# PCB_Emergencia.net
KiCad netlist of a schematic drawn in Altium Designer
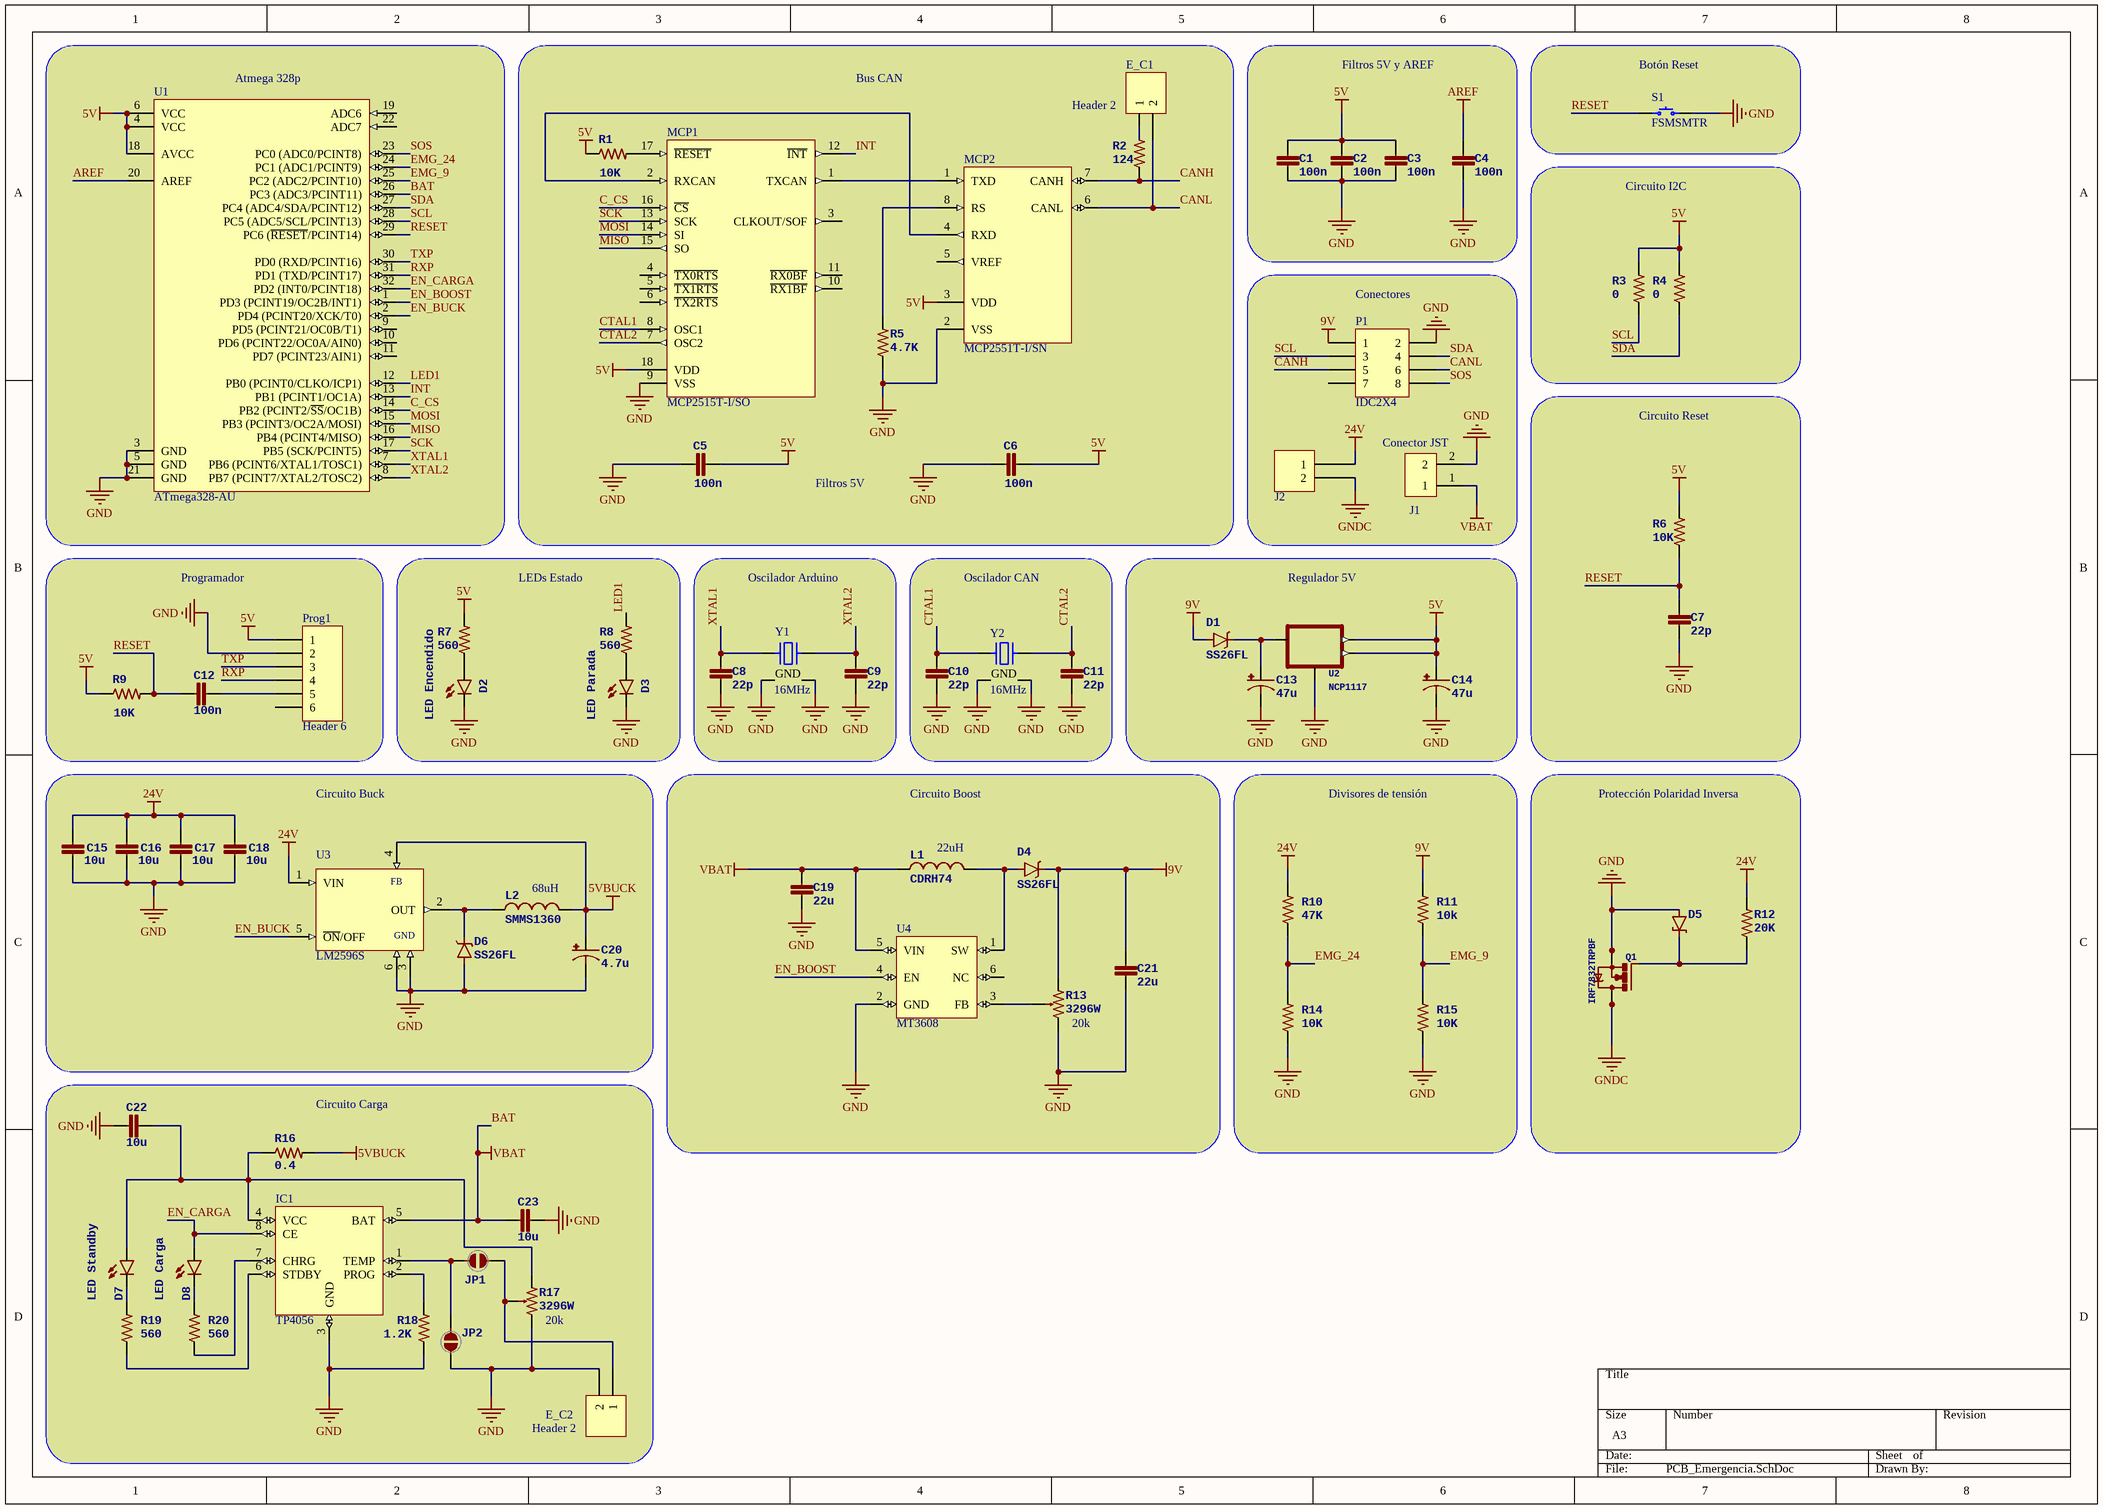
[diagram p0: PCB_Emergencia.SchDoc]

(export (version "E")
  (design (tool "Eeschema 10.0.6"))
  (components
    (comp (ref "C1")
      (value "CapacitorStandard 0603 ceramic capacitor, and 0.1\" leaded capacitor.")
      (footprint "SparkFun-Passives:0805")
      (fields (field (name "CAP") "100n"))
      (libsource (lib "") (part "CAP0805_3"))
    )
    (comp (ref "C2")
      (value "CapacitorStandard 0603 ceramic capacitor, and 0.1\" leaded capacitor.")
      (footprint "SparkFun-Passives:0805")
      (fields (field (name "CAP") "100n"))
      (libsource (lib "") (part "CAP0805_3"))
    )
    (comp (ref "C3")
      (value "CapacitorStandard 0603 ceramic capacitor, and 0.1\" leaded capacitor.")
      (footprint "SparkFun-Passives:0805")
      (fields (field (name "CAP") "100n"))
      (libsource (lib "") (part "CAP0805_3"))
    )
    (comp (ref "C4")
      (value "CapacitorStandard 0603 ceramic capacitor, and 0.1\" leaded capacitor.")
      (footprint "SparkFun-Passives:0805")
      (fields (field (name "CAP") "100n"))
      (libsource (lib "") (part "CAP0805_3"))
    )
    (comp (ref "C5")
      (value "CapacitorStandard 0603 ceramic capacitor, and 0.1\" leaded capacitor.")
      (footprint "SparkFun-Passives:0805")
      (fields (field (name "CAP") "100n"))
      (libsource (lib "") (part "CAP0805_2"))
    )
    (comp (ref "C6")
      (value "CapacitorStandard 0603 ceramic capacitor, and 0.1\" leaded capacitor.")
      (footprint "SparkFun-Passives:0805")
      (fields (field (name "CAP") "100n"))
      (libsource (lib "") (part "CAP0805_2"))
    )
    (comp (ref "C7")
      (value "CapacitorStandard 0603 ceramic capacitor, and 0.1\" leaded capacitor.")
      (footprint "SparkFun-Passives:0805")
      (fields (field (name "CAP") "22p"))
      (libsource (lib "") (part "CAP0805_3"))
    )
    (comp (ref "C8")
      (value "CapacitorStandard 0603 ceramic capacitor, and 0.1\" leaded capacitor.")
      (footprint "SparkFun-Passives:0805")
      (fields (field (name "CAP") "22p"))
      (libsource (lib "") (part "CAP0805_3"))
    )
    (comp (ref "C9")
      (value "CapacitorStandard 0603 ceramic capacitor, and 0.1\" leaded capacitor.")
      (footprint "SparkFun-Passives:0805")
      (fields (field (name "CAP") "22p"))
      (libsource (lib "") (part "CAP0805_1"))
    )
    (comp (ref "C10")
      (value "CapacitorStandard 0603 ceramic capacitor, and 0.1\" leaded capacitor.")
      (footprint "SparkFun-Passives:0805")
      (fields (field (name "CAP") "22p"))
      (libsource (lib "") (part "CAP0805_3"))
    )
    (comp (ref "C11")
      (value "CapacitorStandard 0603 ceramic capacitor, and 0.1\" leaded capacitor.")
      (footprint "SparkFun-Passives:0805")
      (fields (field (name "CAP") "22p"))
      (libsource (lib "") (part "CAP0805_1"))
    )
    (comp (ref "C12")
      (value "CapacitorStandard 0603 ceramic capacitor, and 0.1\" leaded capacitor.")
      (footprint "SparkFun-Passives:0805")
      (fields (field (name "CAP") "100n"))
      (libsource (lib "SparkFun-Capacitors") (part "CAP0805"))
    )
    (comp (ref "C13")
      (value "47u")
      (footprint "PANASONIC_D")
      (libsource (lib "SparkFun-Capacitors") (part "47UF-50V-20%(ELECT)"))
    )
    (comp (ref "C14")
      (value "47u")
      (footprint "PANASONIC_D")
      (libsource (lib "SparkFun-Capacitors") (part "47UF-50V-20%(ELECT)"))
    )
    (comp (ref "C15")
      (value "CapacitorStandard 0603 ceramic capacitor, and 0.1\" leaded capacitor.")
      (footprint "SparkFun-Passives:0805")
      (fields (field (name "CAP") "10u"))
      (libsource (lib "") (part "CAP0805_3"))
    )
    (comp (ref "C16")
      (value "CapacitorStandard 0603 ceramic capacitor, and 0.1\" leaded capacitor.")
      (footprint "SparkFun-Passives:0805")
      (fields (field (name "CAP") "10u"))
      (libsource (lib "") (part "CAP0805_3"))
    )
    (comp (ref "C17")
      (value "CapacitorStandard 0603 ceramic capacitor, and 0.1\" leaded capacitor.")
      (footprint "SparkFun-Passives:0805")
      (fields (field (name "CAP") "10u"))
      (libsource (lib "") (part "CAP0805_3"))
    )
    (comp (ref "C18")
      (value "CapacitorStandard 0603 ceramic capacitor, and 0.1\" leaded capacitor.")
      (footprint "SparkFun-Passives:0805")
      (fields (field (name "CAP") "10u"))
      (libsource (lib "") (part "CAP0805_3"))
    )
    (comp (ref "C19")
      (value "CapacitorStandard 0603 ceramic capacitor, and 0.1\" leaded capacitor.")
      (footprint "SparkFun-Passives:0805")
      (fields (field (name "CAP") "22u"))
      (libsource (lib "") (part "CAP0805_1"))
    )
    (comp (ref "C20")
      (value "4.7u")
      (footprint "PANASONIC_D")
      (libsource (lib "SparkFun-Capacitors") (part "47UF-50V-20%(ELECT)"))
    )
    (comp (ref "C21")
      (value "CapacitorStandard 0603 ceramic capacitor, and 0.1\" leaded capacitor.")
      (footprint "SparkFun-Passives:0805")
      (fields (field (name "CAP") "22u"))
      (libsource (lib "") (part "CAP0805_1"))
    )
    (comp (ref "C22")
      (value "CapacitorStandard 0603 ceramic capacitor, and 0.1\" leaded capacitor.")
      (footprint "SparkFun-Passives:0805")
      (fields (field (name "CAP") "10u"))
      (libsource (lib "SparkFun-Capacitors") (part "CAP0805"))
    )
    (comp (ref "C23")
      (value "CapacitorStandard 0603 ceramic capacitor, and 0.1\" leaded capacitor.")
      (footprint "SparkFun-Passives:0805")
      (fields (field (name "CAP") "10u"))
      (libsource (lib "") (part "CAP0805_2"))
    )
    (comp (ref "D1") (value "SS26FL") (footprint "SS26FL") (libsource (lib "SS26FL") (part "SS26FL")))
    (comp (ref "D2")
      (value "LED Encendido")
      (footprint "LED-1206")
      (libsource (lib "SparkFun-LED") (part "LED1206"))
    )
    (comp (ref "D3")
      (value "LED Parada")
      (footprint "LED-1206")
      (libsource (lib "SparkFun-LED") (part "LED1206"))
    )
    (comp (ref "D4") (value "SS26FL") (footprint "SS26FL") (libsource (lib "SS26FL") (part "SS26FL")))
    (comp (ref "D5")
      (value "13V Zener MM1Z13")
      (footprint "SOD-123")
      (libsource (lib "SparkFun-DiscreteSemi") (part "DIODE-ZENER16V"))
    )
    (comp (ref "D6") (value "SS26FL") (footprint "SS26FL") (libsource (lib "SS26FL") (part "SS26FL")))
    (comp (ref "D7")
      (value "LED Standby")
      (footprint "LED-1206")
      (libsource (lib "SparkFun-LED") (part "LED1206"))
    )
    (comp (ref "D8")
      (value "LED Carga")
      (footprint "LED-1206")
      (libsource (lib "SparkFun-LED") (part "LED1206"))
    )
    (comp (ref "E_C1")
      (value "Header 2")
      (footprint "HDR1X2")
      (description "Header, 2-Pin")
      (fields (field (name "PUBLISHER") "Altium Limited"))
      (libsource (lib "Miscellaneous Connectors") (part "Header 2"))
    )
    (comp (ref "E_C2")
      (value "Header 2")
      (footprint "HDR1X2")
      (description "Header, 2-Pin")
      (fields (field (name "PUBLISHER") "Altium Limited"))
      (libsource (lib "") (part "Header 2_1"))
    )
    (comp (ref "IC1")
      (value "TP4056")
      (footprint "*SOP-8")
      (fields (field (name "MF") "NanJing Top Power ASIC Corp."))
      (libsource (lib "TP4056") (part "TP4056"))
    )
    (comp (ref "J1")
      (value "Conector JST")
      (footprint "*JST_S2B-PH-K-S(LF)(SN)")
      (description "PH Series 2 Position 2.0 mm Through Hole Side Entry Shrouded Header")
      (fields (field (name "MP") "S2B-PH-K-S_LF__SN_") (field (name "MF") "JST Sales"))
      (libsource (lib "S2B-PH-K-S_LF__SN_") (part "S2B-PH-K-S(LF)(SN)"))
    )
    (comp (ref "J2")
      (value "20020110-D021A01LF")
      (footprint "FCI 06-381-2PIN")
      (description "TERM BLOCK HDR 2POS R/A 3.81MM")
      (fields (field (name "MANUFACTURER") "FCI") (field (name "VOLTAGE") "300V"))
      (libsource (lib "Connector - Terminal Block") (part "2 Pin"))
    )
    (comp (ref "JP1")
      (value "JUMPER-PAD-2-NC_BY_PASTE")
      (footprint "PAD-JUMPER-2-NC_BY_PASTE_YES_SILK")
      (libsource (lib "SparkFun-Passives") (part "JUMPER-PAD-2-NC_BY_PASTE"))
    )
    (comp (ref "JP2")
      (value "JUMPER-PAD-2-NC_BY_PASTE")
      (footprint "PAD-JUMPER-2-NC_BY_PASTE_YES_SILK")
      (libsource (lib "SparkFun-Passives") (part "JUMPER-PAD-2-NC_BY_PASTE"))
    )
    (comp (ref "L1")
      (value "CDRH74")
      (footprint "CDRH74")
      (fields (field (name "ALTIUM_VALUE") "22uH"))
      (libsource (lib "CDRH74") (part "CDRH74"))
    )
    (comp (ref "L2")
      (value "SMMS1360")
      (footprint "SMMS1360 - duplicate")
      (fields (field (name "ALTIUM_VALUE") "68uH"))
      (libsource (lib "SMMS1360") (part "INDUCTOR"))
    )
    (comp (ref "MCP1")
      (value "MCP2515T-I/SO")
      (footprint "SOIC-SO18_N")
      (description "Stand-Alone CAN Controller With SPI Interface, 18-Pin SOIC, Industrial Temperature, Tape and Reel")
      (fields (field (name "PUBLISHER") "Altium Limited"))
      (libsource (lib "Microchip Interface") (part "MCP2515T-I/SO"))
    )
    (comp (ref "MCP2")
      (value "MCP2551T-I/SN")
      (footprint "SOIC-SN8_N")
      (description "High-Speed CAN Transceiver, 8-Pin SOIC, Industrial Temperature, Tape and Reel")
      (fields (field (name "PUBLISHER") "Altium Limited"))
      (libsource (lib "Microchip Interface") (part "MCP2551T-I/SN"))
    )
    (comp (ref "P1")
      (value "IDC2X4")
      (footprint "IDC2X4")
      (description "Header, 4-Pin, Dual row")
      (fields (field (name "PUBLISHER") "Altium Limited"))
      (libsource (lib "IDC") (part "IDC2X4"))
    )
    (comp (ref "Prog1")
      (value "Header 6")
      (footprint "HDR1X6")
      (description "Header, 6-Pin")
      (fields (field (name "PUBLISHER") "Altium Limited"))
      (libsource (lib "Miscellaneous Connectors") (part "Header 6"))
    )
    (comp (ref "Q1")
      (value "IRF7832TRPBF")
      (footprint "transistor-power:SO-08")
      (libsource (lib "transistor-power") (part "N-MOSFET-SO8S"))
    )
    (comp (ref "R1")
      (value "ResistorBasic schematic elements and footprints for 0603, 1206, and PTH resistors.")
      (footprint "SparkFun-Passives:0805")
      (fields (field (name "RES") "10K"))
      (libsource (lib "SparkFun-Passives") (part "RESISTOR0805-RES"))
    )
    (comp (ref "R2")
      (value "ResistorBasic schematic elements and footprints for 0603, 1206, and PTH resistors.")
      (footprint "SparkFun-Passives:0805")
      (fields (field (name "RES") "124"))
      (libsource (lib "SparkFun-Passives") (part "RESISTOR0805-RES"))
    )
    (comp (ref "R3")
      (value "ResistorBasic schematic elements and footprints for 0603, 1206, and PTH resistors.")
      (footprint "SparkFun-Passives:0805")
      (fields (field (name "RES") "0"))
      (libsource (lib "SparkFun-Passives") (part "RESISTOR0805-RES"))
    )
    (comp (ref "R4")
      (value "ResistorBasic schematic elements and footprints for 0603, 1206, and PTH resistors.")
      (footprint "SparkFun-Passives:0805")
      (fields (field (name "RES") "0"))
      (libsource (lib "SparkFun-Passives") (part "RESISTOR0805-RES"))
    )
    (comp (ref "R5")
      (value "ResistorBasic schematic elements and footprints for 0603, 1206, and PTH resistors.")
      (footprint "SparkFun-Passives:0805")
      (fields (field (name "RES") "4.7K"))
      (libsource (lib "SparkFun-Passives") (part "RESISTOR0805-RES"))
    )
    (comp (ref "R6")
      (value "ResistorBasic schematic elements and footprints for 0603, 1206, and PTH resistors.")
      (footprint "SparkFun-Passives:0805")
      (fields (field (name "RES") "10K"))
      (libsource (lib "SparkFun-Passives") (part "RESISTOR0805-RES"))
    )
    (comp (ref "R7")
      (value "ResistorBasic schematic elements and footprints for 0603, 1206, and PTH resistors.")
      (footprint "SparkFun-Passives:0805")
      (fields (field (name "RES") "560"))
      (libsource (lib "SparkFun-Passives") (part "RESISTOR0805-RES"))
    )
    (comp (ref "R8")
      (value "ResistorBasic schematic elements and footprints for 0603, 1206, and PTH resistors.")
      (footprint "SparkFun-Passives:0805")
      (fields (field (name "RES") "560"))
      (libsource (lib "SparkFun-Passives") (part "RESISTOR0805-RES"))
    )
    (comp (ref "R9")
      (value "ResistorBasic schematic elements and footprints for 0603, 1206, and PTH resistors.")
      (footprint "SparkFun-Passives:0805")
      (fields (field (name "RES") "10K"))
      (libsource (lib "SparkFun-Passives") (part "RESISTOR0805-RES"))
    )
    (comp (ref "R10")
      (value "ResistorBasic schematic elements and footprints for 0603, 1206, and PTH resistors.")
      (footprint "SparkFun-Passives:0805")
      (fields (field (name "RES") "47K"))
      (libsource (lib "SparkFun-Passives") (part "RESISTOR0805-RES"))
    )
    (comp (ref "R11")
      (value "ResistorBasic schematic elements and footprints for 0603, 1206, and PTH resistors.")
      (footprint "SparkFun-Passives:0805")
      (fields (field (name "RES") "10k"))
      (libsource (lib "SparkFun-Passives") (part "RESISTOR0805-RES"))
    )
    (comp (ref "R12")
      (value "20K")
      (footprint "SparkFun-Passives:0805")
      (libsource (lib "SparkFun-Passives") (part "RESISTOR0805-RES"))
    )
    (comp (ref "R13")
      (value "3296W")
      (footprint "3296W")
      (fields (field (name "ALTIUM_VALUE") "20k"))
      (libsource (lib "3296W") (part "3296W"))
    )
    (comp (ref "R14")
      (value "ResistorBasic schematic elements and footprints for 0603, 1206, and PTH resistors.")
      (footprint "SparkFun-Passives:0805")
      (fields (field (name "RES") "10K"))
      (libsource (lib "SparkFun-Passives") (part "RESISTOR0805-RES"))
    )
    (comp (ref "R15")
      (value "ResistorBasic schematic elements and footprints for 0603, 1206, and PTH resistors.")
      (footprint "SparkFun-Passives:0805")
      (fields (field (name "RES") "10K"))
      (libsource (lib "SparkFun-Passives") (part "RESISTOR0805-RES"))
    )
    (comp (ref "R16")
      (value "ResistorBasic schematic elements and footprints for 0603, 1206, and PTH resistors.")
      (footprint "SparkFun-Passives:0805")
      (fields (field (name "RES") "0.4"))
      (libsource (lib "SparkFun-Passives") (part "RESISTOR0805-RES"))
    )
    (comp (ref "R17")
      (value "3296W")
      (footprint "3296W")
      (fields (field (name "ALTIUM_VALUE") "20k"))
      (libsource (lib "3296W") (part "3296W"))
    )
    (comp (ref "R18")
      (value "ResistorBasic schematic elements and footprints for 0603, 1206, and PTH resistors.")
      (footprint "SparkFun-Passives:0805")
      (fields (field (name "RES") "1.2K"))
      (libsource (lib "SparkFun-Passives") (part "RESISTOR0805-RES"))
    )
    (comp (ref "R19")
      (value "ResistorBasic schematic elements and footprints for 0603, 1206, and PTH resistors.")
      (footprint "SparkFun-Passives:0805")
      (fields (field (name "RES") "560"))
      (libsource (lib "SparkFun-Passives") (part "RESISTOR0805-RES"))
    )
    (comp (ref "R20")
      (value "ResistorBasic schematic elements and footprints for 0603, 1206, and PTH resistors.")
      (footprint "SparkFun-Passives:0805")
      (fields (field (name "RES") "560"))
      (libsource (lib "SparkFun-Passives") (part "RESISTOR0805-RES"))
    )
    (comp (ref "S1")
      (value "FSMSMTR")
      (footprint "TE FSMSMTR")
      (description "SWITCH TACTILE SPST-NO 0.05A 24V")
      (fields (field (name "MANUFACTURER") "TE Connectivity Alcoswitch Switches"))
      (libsource (lib "Button - Tactile") (part "SPST-NO 2 PIN"))
    )
    (comp (ref "U1")
      (value "ATmega328-AU")
      (footprint "32A_N")
      (fields (field (name "PUBLISHER") "Altium Limited"))
      (libsource (lib "Atmel Microcontroller 8-Bit megaAVR") (part "ATmega328-AU"))
    )
    (comp (ref "U2")
      (value "NCP1117")
      (footprint "SOT223")
      (libsource (lib "SparkFun-IC-Power") (part "V_REG_LM1117SOT223"))
    )
    (comp (ref "U3")
      (value "LM2596S")
      (footprint "LM2596S")
      (description "Semiconductors and Actives")
      (fields (field (name "MF") "Texas Instruments"))
      (libsource (lib "LM2596S") (part "LM2596S"))
    )
    (comp (ref "U4")
      (value "MT3608")
      (footprint "*SOT23-6")
      (description "High Efficiency 1.2MHz\r\n2A Step Up Converter")
      (fields (field (name "MF") "Aerosemi Technology Co., Ltd"))
      (libsource (lib "MT3608") (part "MT3608"))
    )
    (comp (ref "Y1")
      (value "16MHz")
      (footprint "NDK NX3225SA")
      (description "CRYSTAL 16.0000MHZ 8PF SMD")
      (fields (field (name "PART NUMBER") "NX3225SA-16.000MHZ-STD-CSR-1") (field (name "MANUFACTURER") "NDK"))
      (libsource (lib "Oscillator - Crystal") (part "NX3225SA-16.000MHZ-STD-CSR-1"))
    )
    (comp (ref "Y2")
      (value "16MHz")
      (footprint "NDK NX3225SA")
      (description "CRYSTAL 16.0000MHZ 8PF SMD")
      (fields (field (name "PART NUMBER") "NX3225SA-16.000MHZ-STD-CSR-1") (field (name "MANUFACTURER") "NDK"))
      (libsource (lib "Oscillator - Crystal") (part "NX3225SA-16.000MHZ-STD-CSR-1"))
    )
  )
  (nets
    (net (code "1") (name "/CANH") (class "Default")
      (node (ref "MCP2") (pin "7") (pinfunction "CANH_7") (pintype "bidirectional"))
      (node (ref "P1") (pin "5") (pinfunction "5_5") (pintype "passive"))
      (node (ref "R2") (pin "1") (pinfunction "1_1") (pintype "passive"))
    )
    (net (code "2") (name "/CANL") (class "Default")
      (node (ref "E_C1") (pin "2") (pinfunction "2_2") (pintype "passive"))
      (node (ref "MCP2") (pin "6") (pinfunction "CANL_6") (pintype "bidirectional"))
      (node (ref "P1") (pin "6") (pinfunction "6_6") (pintype "passive"))
    )
    (net (code "3") (name "/CTAL1") (class "Default")
      (node (ref "C10") (pin "2") (pinfunction "2_2") (pintype "passive"))
      (node (ref "MCP1") (pin "8") (pinfunction "OSC1_8") (pintype "input"))
      (node (ref "Y2") (pin "1") (pinfunction "1_1") (pintype "passive"))
    )
    (net (code "4") (name "/CTAL2") (class "Default")
      (node (ref "C11") (pin "1") (pinfunction "1_1") (pintype "passive"))
      (node (ref "MCP1") (pin "7") (pinfunction "OSC2_7") (pintype "output"))
      (node (ref "Y2") (pin "3") (pinfunction "3_3") (pintype "passive"))
    )
    (net (code "5") (name "/C_CS") (class "Default")
      (node (ref "MCP1") (pin "16") (pinfunction "~{CS}_16") (pintype "input"))
      (node (ref "U1") (pin "14") (pinfunction "PB2_(PCINT2/~{SS}/OC1B)_14") (pintype "bidirectional"))
    )
    (net (code "6") (name "/EMG_9") (class "Default")
      (node (ref "R11") (pin "1") (pinfunction "1_1") (pintype "passive"))
      (node (ref "R15") (pin "2") (pinfunction "2_2") (pintype "passive"))
      (node (ref "U1") (pin "25") (pinfunction "PC2_(ADC2/PCINT10)_25") (pintype "bidirectional"))
    )
    (net (code "7") (name "/EMG_24") (class "Default")
      (node (ref "R10") (pin "1") (pinfunction "1_1") (pintype "passive"))
      (node (ref "R14") (pin "2") (pinfunction "2_2") (pintype "passive"))
      (node (ref "U1") (pin "24") (pinfunction "PC1_(ADC1/PCINT9)_24") (pintype "bidirectional"))
    )
    (net (code "8") (name "/EN_BOOST") (class "Default")
      (node (ref "U1") (pin "1") (pinfunction "PD3_(PCINT19/OC2B/INT1)_1") (pintype "bidirectional"))
      (node (ref "U4") (pin "4") (pinfunction "EN_4") (pintype "bidirectional"))
    )
    (net (code "9") (name "/EN_BUCK") (class "Default")
      (node (ref "U1") (pin "2") (pinfunction "PD4_(PCINT20/XCK/T0)_2") (pintype "bidirectional"))
      (node (ref "U3") (pin "5") (pinfunction "~{ON}/OFF_5") (pintype "input"))
    )
    (net (code "10") (name "/EN_CARGA") (class "Default")
      (node (ref "D8") (pin "A") (pinfunction "A_A") (pintype "passive"))
      (node (ref "IC1") (pin "8") (pinfunction "CE_8") (pintype "bidirectional"))
      (node (ref "U1") (pin "32") (pinfunction "PD2_(INT0/PCINT18)_32") (pintype "bidirectional"))
    )
    (net (code "11") (name "/INT") (class "Default")
      (node (ref "MCP1") (pin "12") (pinfunction "~{INT}_12") (pintype "output"))
      (node (ref "U1") (pin "13") (pinfunction "PB1_(PCINT1/OC1A)_13") (pintype "bidirectional"))
    )
    (net (code "12") (name "/LED1") (class "Default")
      (node (ref "R8") (pin "2") (pinfunction "2_2") (pintype "passive"))
      (node (ref "U1") (pin "12") (pinfunction "PB0_(PCINT0/CLKO/ICP1)_12") (pintype "bidirectional"))
    )
    (net (code "13") (name "/MISO") (class "Default")
      (node (ref "MCP1") (pin "15") (pinfunction "SO_15") (pintype "output"))
      (node (ref "U1") (pin "16") (pinfunction "PB4_(PCINT4/MISO)_16") (pintype "bidirectional"))
    )
    (net (code "14") (name "/MOSI") (class "Default")
      (node (ref "MCP1") (pin "14") (pinfunction "SI_14") (pintype "input"))
      (node (ref "U1") (pin "15") (pinfunction "PB3_(PCINT3/OC2A/MOSI)_15") (pintype "bidirectional"))
    )
    (net (code "15") (name "/RESET") (class "Default")
      (node (ref "C12") (pin "2") (pinfunction "2_2") (pintype "passive"))
      (node (ref "C7") (pin "2") (pinfunction "2_2") (pintype "passive"))
      (node (ref "R6") (pin "1") (pinfunction "1_1") (pintype "passive"))
      (node (ref "R9") (pin "2") (pinfunction "2_2") (pintype "passive"))
      (node (ref "S1") (pin "1") (pinfunction "1_1") (pintype "passive"))
      (node (ref "U1") (pin "29") (pinfunction "PC6_(~{RESET}/PCINT14)_29") (pintype "bidirectional"))
    )
    (net (code "16") (name "/RXP") (class "Default")
      (node (ref "Prog1") (pin "4") (pinfunction "4_4") (pintype "passive"))
      (node (ref "U1") (pin "31") (pinfunction "PD1_(TXD/PCINT17)_31") (pintype "bidirectional"))
    )
    (net (code "17") (name "/SCK") (class "Default")
      (node (ref "MCP1") (pin "13") (pinfunction "SCK_13") (pintype "input"))
      (node (ref "U1") (pin "17") (pinfunction "PB5_(SCK/PCINT5)_17") (pintype "bidirectional"))
    )
    (net (code "18") (name "/SCL") (class "Default")
      (node (ref "P1") (pin "3") (pinfunction "3_3") (pintype "passive"))
      (node (ref "R3") (pin "1") (pinfunction "1_1") (pintype "passive"))
      (node (ref "U1") (pin "28") (pinfunction "PC5_(ADC5/SCL/PCINT13)_28") (pintype "bidirectional"))
    )
    (net (code "19") (name "/SDA") (class "Default")
      (node (ref "P1") (pin "4") (pinfunction "4_4") (pintype "passive"))
      (node (ref "R4") (pin "1") (pinfunction "1_1") (pintype "passive"))
      (node (ref "U1") (pin "27") (pinfunction "PC4_(ADC4/SDA/PCINT12)_27") (pintype "bidirectional"))
    )
    (net (code "20") (name "/SOS") (class "Default")
      (node (ref "P1") (pin "8") (pinfunction "8_8") (pintype "passive"))
      (node (ref "U1") (pin "23") (pinfunction "PC0_(ADC0/PCINT8)_23") (pintype "bidirectional"))
    )
    (net (code "21") (name "/TXP") (class "Default")
      (node (ref "Prog1") (pin "3") (pinfunction "3_3") (pintype "passive"))
      (node (ref "U1") (pin "30") (pinfunction "PD0_(RXD/PCINT16)_30") (pintype "bidirectional"))
    )
    (net (code "22") (name "/XTAL1") (class "Default")
      (node (ref "C8") (pin "2") (pinfunction "2_2") (pintype "passive"))
      (node (ref "U1") (pin "7") (pinfunction "PB6_(PCINT6/XTAL1/TOSC1)_7") (pintype "bidirectional"))
      (node (ref "Y1") (pin "1") (pinfunction "1_1") (pintype "passive"))
    )
    (net (code "23") (name "/XTAL2") (class "Default")
      (node (ref "C9") (pin "1") (pinfunction "1_1") (pintype "passive"))
      (node (ref "U1") (pin "8") (pinfunction "PB7_(PCINT7/XTAL2/TOSC2)_8") (pintype "bidirectional"))
      (node (ref "Y1") (pin "3") (pinfunction "3_3") (pintype "passive"))
    )
    (net (code "24") (name "5V") (class "Default")
      (node (ref "C1") (pin "2") (pinfunction "2_2") (pintype "passive"))
      (node (ref "C14") (pin "+") (pinfunction "+_+") (pintype "passive"))
      (node (ref "C2") (pin "2") (pinfunction "2_2") (pintype "passive"))
      (node (ref "C3") (pin "2") (pinfunction "2_2") (pintype "passive"))
      (node (ref "C5") (pin "2") (pinfunction "2_2") (pintype "passive"))
      (node (ref "C6") (pin "2") (pinfunction "2_2") (pintype "passive"))
      (node (ref "MCP1") (pin "18") (pinfunction "VDD_18") (pintype "power_in"))
      (node (ref "MCP2") (pin "3") (pinfunction "VDD_3") (pintype "power_in"))
      (node (ref "Prog1") (pin "1") (pinfunction "1_1") (pintype "passive"))
      (node (ref "R1") (pin "1") (pinfunction "1_1") (pintype "passive"))
      (node (ref "R3") (pin "2") (pinfunction "2_2") (pintype "passive"))
      (node (ref "R4") (pin "2") (pinfunction "2_2") (pintype "passive"))
      (node (ref "R6") (pin "2") (pinfunction "2_2") (pintype "passive"))
      (node (ref "R7") (pin "2") (pinfunction "2_2") (pintype "passive"))
      (node (ref "R9") (pin "1") (pinfunction "1_1") (pintype "passive"))
      (node (ref "U1") (pin "18") (pinfunction "AVCC_18") (pintype "power_in"))
      (node (ref "U1") (pin "4") (pinfunction "VCC_4") (pintype "power_in"))
      (node (ref "U1") (pin "6") (pinfunction "VCC_6") (pintype "power_in"))
      (node (ref "U2") (pin "2") (pinfunction "OUT_2") (pintype "output"))
      (node (ref "U2") (pin "4") (pinfunction "OUT@1_4") (pintype "output"))
    )
    (net (code "25") (name "5VBUCK") (class "Default")
      (node (ref "C20") (pin "+") (pinfunction "+_+") (pintype "passive"))
      (node (ref "L2") (pin "PS2") (pinfunction "2_PS2") (pintype "passive"))
      (node (ref "R16") (pin "2") (pinfunction "2_2") (pintype "passive"))
      (node (ref "U3") (pin "4") (pinfunction "FB_4") (pintype "input"))
    )
    (net (code "26") (name "9V") (class "Default")
      (node (ref "C21") (pin "1") (pinfunction "1_1") (pintype "passive"))
      (node (ref "D1") (pin "A") (pinfunction "A_A") (pintype "passive"))
      (node (ref "D4") (pin "C") (pinfunction "C_C") (pintype "passive"))
      (node (ref "P1") (pin "1") (pinfunction "1_1") (pintype "passive"))
      (node (ref "R11") (pin "2") (pinfunction "2_2") (pintype "passive"))
      (node (ref "R13") (pin "1") (pinfunction "1_1") (pintype "passive"))
    )
    (net (code "27") (name "24V") (class "Default")
      (node (ref "C15") (pin "2") (pinfunction "2_2") (pintype "passive"))
      (node (ref "C16") (pin "2") (pinfunction "2_2") (pintype "passive"))
      (node (ref "C17") (pin "2") (pinfunction "2_2") (pintype "passive"))
      (node (ref "C18") (pin "2") (pinfunction "2_2") (pintype "passive"))
      (node (ref "J2") (pin "1") (pinfunction "1_1") (pintype "passive"))
      (node (ref "R10") (pin "2") (pinfunction "2_2") (pintype "passive"))
      (node (ref "R12") (pin "2") (pinfunction "2_2") (pintype "passive"))
      (node (ref "U3") (pin "1") (pinfunction "VIN_1") (pintype "input"))
    )
    (net (code "28") (name "AREF") (class "Default")
      (node (ref "C4") (pin "2") (pinfunction "2_2") (pintype "passive"))
      (node (ref "U1") (pin "20") (pinfunction "AREF_20") (pintype "passive"))
    )
    (net (code "29") (name "GND") (class "Default")
      (node (ref "C1") (pin "1") (pinfunction "1_1") (pintype "passive"))
      (node (ref "C10") (pin "1") (pinfunction "1_1") (pintype "passive"))
      (node (ref "C11") (pin "2") (pinfunction "2_2") (pintype "passive"))
      (node (ref "C13") (pin "-") (pinfunction "-_-") (pintype "passive"))
      (node (ref "C14") (pin "-") (pinfunction "-_-") (pintype "passive"))
      (node (ref "C15") (pin "1") (pinfunction "1_1") (pintype "passive"))
      (node (ref "C16") (pin "1") (pinfunction "1_1") (pintype "passive"))
      (node (ref "C17") (pin "1") (pinfunction "1_1") (pintype "passive"))
      (node (ref "C18") (pin "1") (pinfunction "1_1") (pintype "passive"))
      (node (ref "C19") (pin "2") (pinfunction "2_2") (pintype "passive"))
      (node (ref "C2") (pin "1") (pinfunction "1_1") (pintype "passive"))
      (node (ref "C20") (pin "-") (pinfunction "-_-") (pintype "passive"))
      (node (ref "C21") (pin "2") (pinfunction "2_2") (pintype "passive"))
      (node (ref "C22") (pin "2") (pinfunction "2_2") (pintype "passive"))
      (node (ref "C23") (pin "2") (pinfunction "2_2") (pintype "passive"))
      (node (ref "C3") (pin "1") (pinfunction "1_1") (pintype "passive"))
      (node (ref "C4") (pin "1") (pinfunction "1_1") (pintype "passive"))
      (node (ref "C5") (pin "1") (pinfunction "1_1") (pintype "passive"))
      (node (ref "C6") (pin "1") (pinfunction "1_1") (pintype "passive"))
      (node (ref "C7") (pin "1") (pinfunction "1_1") (pintype "passive"))
      (node (ref "C8") (pin "1") (pinfunction "1_1") (pintype "passive"))
      (node (ref "C9") (pin "2") (pinfunction "2_2") (pintype "passive"))
      (node (ref "D2") (pin "C") (pinfunction "C_C") (pintype "passive"))
      (node (ref "D3") (pin "C") (pinfunction "C_C") (pintype "passive"))
      (node (ref "D5") (pin "A") (pinfunction "A_A") (pintype "passive"))
      (node (ref "D6") (pin "A") (pinfunction "A_A") (pintype "passive"))
      (node (ref "E_C2") (pin "2") (pinfunction "2_2") (pintype "passive"))
      (node (ref "IC1") (pin "3") (pinfunction "GND_3") (pintype "bidirectional"))
      (node (ref "J1") (pin "2") (pinfunction "2_2") (pintype "passive"))
      (node (ref "JP2") (pin "1") (pinfunction "1_1") (pintype "passive"))
      (node (ref "MCP1") (pin "9") (pinfunction "VSS_9") (pintype "power_in"))
      (node (ref "MCP2") (pin "2") (pinfunction "VSS_2") (pintype "power_in"))
      (node (ref "P1") (pin "2") (pinfunction "2_2") (pintype "passive"))
      (node (ref "Prog1") (pin "2") (pinfunction "2_2") (pintype "passive"))
      (node (ref "Q1") (pin "1") (pinfunction "S_1") (pintype "passive"))
      (node (ref "Q1") (pin "2") (pinfunction "S_2") (pintype "passive"))
      (node (ref "Q1") (pin "3") (pinfunction "S_3") (pintype "passive"))
      (node (ref "R13") (pin "3") (pinfunction "3_3") (pintype "passive"))
      (node (ref "R14") (pin "1") (pinfunction "1_1") (pintype "passive"))
      (node (ref "R15") (pin "1") (pinfunction "1_1") (pintype "passive"))
      (node (ref "R17") (pin "3") (pinfunction "3_3") (pintype "passive"))
      (node (ref "R18") (pin "1") (pinfunction "1_1") (pintype "passive"))
      (node (ref "R5") (pin "1") (pinfunction "1_1") (pintype "passive"))
      (node (ref "S1") (pin "2") (pinfunction "2_2") (pintype "passive"))
      (node (ref "U1") (pin "21") (pinfunction "GND_21") (pintype "power_in"))
      (node (ref "U1") (pin "3") (pinfunction "GND_3") (pintype "power_in"))
      (node (ref "U1") (pin "5") (pinfunction "GND_5") (pintype "power_in"))
      (node (ref "U2") (pin "1") (pinfunction "ADJ_1") (pintype "passive"))
      (node (ref "U3") (pin "3") (pinfunction "GND_3") (pintype "input"))
      (node (ref "U3") (pin "6") (pinfunction "GND@6_6") (pintype "input"))
      (node (ref "U4") (pin "2") (pinfunction "GND_2") (pintype "bidirectional"))
      (node (ref "Y1") (pin "2") (pinfunction "GND_2") (pintype "passive"))
      (node (ref "Y1") (pin "4") (pinfunction "GND_4") (pintype "passive"))
      (node (ref "Y2") (pin "2") (pinfunction "GND_2") (pintype "passive"))
      (node (ref "Y2") (pin "4") (pinfunction "GND_4") (pintype "passive"))
    )
    (net (code "30") (name "GNDC") (class "Default")
      (node (ref "J2") (pin "2") (pinfunction "2_2") (pintype "passive"))
      (node (ref "Q1") (pin "5") (pinfunction "D_5") (pintype "passive"))
      (node (ref "Q1") (pin "6") (pinfunction "D_6") (pintype "passive"))
      (node (ref "Q1") (pin "7") (pinfunction "D_7") (pintype "passive"))
      (node (ref "Q1") (pin "8") (pinfunction "D_8") (pintype "passive"))
    )
    (net (code "31") (name "Net-(C12-Pad1)") (class "Default")
      (node (ref "C12") (pin "1") (pinfunction "1_1") (pintype "passive"))
      (node (ref "Prog1") (pin "5") (pinfunction "5_5") (pintype "passive"))
    )
    (net (code "32") (name "Net-(D2-PadA)") (class "Default")
      (node (ref "D2") (pin "A") (pinfunction "A_A") (pintype "passive"))
      (node (ref "R7") (pin "1") (pinfunction "1_1") (pintype "passive"))
    )
    (net (code "33") (name "Net-(D3-PadA)") (class "Default")
      (node (ref "D3") (pin "A") (pinfunction "A_A") (pintype "passive"))
      (node (ref "R8") (pin "1") (pinfunction "1_1") (pintype "passive"))
    )
    (net (code "34") (name "Net-(D7-PadC)") (class "Default")
      (node (ref "D7") (pin "C") (pinfunction "C_C") (pintype "passive"))
      (node (ref "R19") (pin "2") (pinfunction "2_2") (pintype "passive"))
    )
    (net (code "35") (name "Net-(D8-PadC)") (class "Default")
      (node (ref "D8") (pin "C") (pinfunction "C_C") (pintype "passive"))
      (node (ref "R20") (pin "2") (pinfunction "2_2") (pintype "passive"))
    )
    (net (code "36") (name "Net-(E_C1-Pad1)") (class "Default")
      (node (ref "E_C1") (pin "1") (pinfunction "1_1") (pintype "passive"))
      (node (ref "R2") (pin "2") (pinfunction "2_2") (pintype "passive"))
    )
    (net (code "37") (name "Net-(E_C2-Pad1)") (class "Default")
      (node (ref "E_C2") (pin "1") (pinfunction "1_1") (pintype "passive"))
      (node (ref "JP1") (pin "2") (pinfunction "2_2") (pintype "passive"))
      (node (ref "R17") (pin "2") (pinfunction "2_2") (pintype "passive"))
    )
    (net (code "38") (name "Net-(IC1-CHRG)") (class "Default")
      (node (ref "IC1") (pin "7") (pinfunction "CHRG_7") (pintype "bidirectional"))
      (node (ref "R20") (pin "1") (pinfunction "1_1") (pintype "passive"))
    )
    (net (code "39") (name "Net-(IC1-PROG)") (class "Default")
      (node (ref "IC1") (pin "2") (pinfunction "PROG_2") (pintype "bidirectional"))
      (node (ref "R18") (pin "2") (pinfunction "2_2") (pintype "passive"))
    )
    (net (code "40") (name "Net-(IC1-STDBY)") (class "Default")
      (node (ref "IC1") (pin "6") (pinfunction "STDBY_6") (pintype "bidirectional"))
      (node (ref "R19") (pin "1") (pinfunction "1_1") (pintype "passive"))
    )
    (net (code "41") (name "Net-(IC1-TEMP)") (class "Default")
      (node (ref "IC1") (pin "1") (pinfunction "TEMP_1") (pintype "bidirectional"))
      (node (ref "JP1") (pin "1") (pinfunction "1_1") (pintype "passive"))
      (node (ref "JP2") (pin "2") (pinfunction "2_2") (pintype "passive"))
    )
    (net (code "42") (name "Net-(IC1-VCC)") (class "Default")
      (node (ref "C22") (pin "1") (pinfunction "1_1") (pintype "passive"))
      (node (ref "D7") (pin "A") (pinfunction "A_A") (pintype "passive"))
      (node (ref "IC1") (pin "4") (pinfunction "VCC_4") (pintype "bidirectional"))
      (node (ref "R16") (pin "1") (pinfunction "1_1") (pintype "passive"))
      (node (ref "R17") (pin "1") (pinfunction "1_1") (pintype "passive"))
    )
    (net (code "43") (name "Net-(L2-1)") (class "Default")
      (node (ref "D6") (pin "C") (pinfunction "C_C") (pintype "passive"))
      (node (ref "L2") (pin "PS1") (pinfunction "1_PS1") (pintype "passive"))
      (node (ref "U3") (pin "2") (pinfunction "OUT_2") (pintype "output"))
    )
    (net (code "44") (name "Net-(MCP1-RXCAN)") (class "Default")
      (node (ref "MCP1") (pin "2") (pinfunction "RXCAN_2") (pintype "input"))
      (node (ref "MCP2") (pin "4") (pinfunction "RXD_4") (pintype "output"))
    )
    (net (code "45") (name "Net-(MCP1-TXCAN)") (class "Default")
      (node (ref "MCP1") (pin "1") (pinfunction "TXCAN_1") (pintype "output"))
      (node (ref "MCP2") (pin "1") (pinfunction "TXD_1") (pintype "input"))
    )
    (net (code "46") (name "Net-(MCP1-~{RESET})") (class "Default")
      (node (ref "MCP1") (pin "17") (pinfunction "~{RESET}_17") (pintype "input"))
      (node (ref "R1") (pin "2") (pinfunction "2_2") (pintype "passive"))
    )
    (net (code "47") (name "Net-(MCP2-RS)") (class "Default")
      (node (ref "MCP2") (pin "8") (pinfunction "RS_8") (pintype "input"))
      (node (ref "R5") (pin "2") (pinfunction "2_2") (pintype "passive"))
    )
    (net (code "48") (name "Net-(Q1-G)") (class "Default")
      (node (ref "D5") (pin "C") (pinfunction "C_C") (pintype "passive"))
      (node (ref "Q1") (pin "4") (pinfunction "G_4") (pintype "passive"))
      (node (ref "R12") (pin "1") (pinfunction "1_1") (pintype "passive"))
    )
    (net (code "49") (name "Net-(U2-IN)") (class "Default")
      (node (ref "C13") (pin "+") (pinfunction "+_+") (pintype "passive"))
      (node (ref "D1") (pin "C") (pinfunction "C_C") (pintype "passive"))
      (node (ref "U2") (pin "3") (pinfunction "IN_3") (pintype "passive"))
    )
    (net (code "50") (name "Net-(U4-FB)") (class "Default")
      (node (ref "R13") (pin "2") (pinfunction "2_2") (pintype "passive"))
      (node (ref "U4") (pin "3") (pinfunction "FB_3") (pintype "bidirectional"))
    )
    (net (code "51") (name "Net-(U4-SW)") (class "Default")
      (node (ref "D4") (pin "A") (pinfunction "A_A") (pintype "passive"))
      (node (ref "L1") (pin "2") (pinfunction "2_2") (pintype "passive"))
      (node (ref "U4") (pin "1") (pinfunction "SW_1") (pintype "bidirectional"))
    )
    (net (code "52") (name "VBAT") (class "Default")
      (node (ref "C19") (pin "1") (pinfunction "1_1") (pintype "passive"))
      (node (ref "C23") (pin "1") (pinfunction "1_1") (pintype "passive"))
      (node (ref "IC1") (pin "5") (pinfunction "BAT_5") (pintype "bidirectional"))
      (node (ref "J1") (pin "1") (pinfunction "1_1") (pintype "passive"))
      (node (ref "L1") (pin "1") (pinfunction "1_1") (pintype "passive"))
      (node (ref "U1") (pin "26") (pinfunction "PC3_(ADC3/PCINT11)_26") (pintype "bidirectional"))
      (node (ref "U4") (pin "5") (pinfunction "VIN_5") (pintype "bidirectional"))
    )
    (net (code "53") (name "unconnected-(MCP1-CLKOUT{slash}SOF-Pad3)") (class "Default")
      (node (ref "MCP1") (pin "3") (pinfunction "CLKOUT/SOF_3") (pintype "output"))
    )
    (net (code "54") (name "unconnected-(MCP1-~{RX0BF}-Pad11)") (class "Default")
      (node (ref "MCP1") (pin "11") (pinfunction "~{RX0BF}_11") (pintype "output"))
    )
    (net (code "55") (name "unconnected-(MCP1-~{RX1BF}-Pad10)") (class "Default")
      (node (ref "MCP1") (pin "10") (pinfunction "~{RX1BF}_10") (pintype "output"))
    )
    (net (code "56") (name "unconnected-(MCP1-~{TX0RTS}-Pad4)") (class "Default")
      (node (ref "MCP1") (pin "4") (pinfunction "~{TX0RTS}_4") (pintype "input"))
    )
    (net (code "57") (name "unconnected-(MCP1-~{TX1RTS}-Pad5)") (class "Default")
      (node (ref "MCP1") (pin "5") (pinfunction "~{TX1RTS}_5") (pintype "input"))
    )
    (net (code "58") (name "unconnected-(MCP1-~{TX2RTS}-Pad6)") (class "Default")
      (node (ref "MCP1") (pin "6") (pinfunction "~{TX2RTS}_6") (pintype "input"))
    )
    (net (code "59") (name "unconnected-(MCP2-VREF-Pad5)") (class "Default")
      (node (ref "MCP2") (pin "5") (pinfunction "VREF_5") (pintype "output"))
    )
    (net (code "60") (name "unconnected-(P1-Pad7)") (class "Default")
      (node (ref "P1") (pin "7") (pinfunction "7_7") (pintype "passive"))
    )
    (net (code "61") (name "unconnected-(Prog1-Pad6)") (class "Default")
      (node (ref "Prog1") (pin "6") (pinfunction "6_6") (pintype "passive"))
    )
    (net (code "62") (name "unconnected-(U1-ADC6-Pad19)") (class "Default")
      (node (ref "U1") (pin "19") (pinfunction "ADC6_19") (pintype "input"))
    )
    (net (code "63") (name "unconnected-(U1-ADC7-Pad22)") (class "Default")
      (node (ref "U1") (pin "22") (pinfunction "ADC7_22") (pintype "input"))
    )
    (net (code "64") (name "unconnected-(U1-PD5_(PCINT21{slash}OC0B{slash}T1)-Pad9)") (class "Default")
      (node (ref "U1") (pin "9") (pinfunction "PD5_(PCINT21/OC0B/T1)_9") (pintype "bidirectional"))
    )
    (net (code "65") (name "unconnected-(U1-PD6_(PCINT22{slash}OC0A{slash}AIN0)-Pad10)") (class "Default")
      (node (ref "U1") (pin "10") (pinfunction "PD6_(PCINT22/OC0A/AIN0)_10") (pintype "bidirectional"))
    )
    (net (code "66") (name "unconnected-(U1-PD7_(PCINT23{slash}AIN1)-Pad11)") (class "Default")
      (node (ref "U1") (pin "11") (pinfunction "PD7_(PCINT23/AIN1)_11") (pintype "bidirectional"))
    )
    (net (code "67") (name "unconnected-(U4-NC-Pad6)") (class "Default")
      (node (ref "U4") (pin "6") (pinfunction "NC_6") (pintype "bidirectional"))
    )
  )
)
